# miniPCIE_Connector.net
KiCad netlist of a schematic drawn in Altium Designer
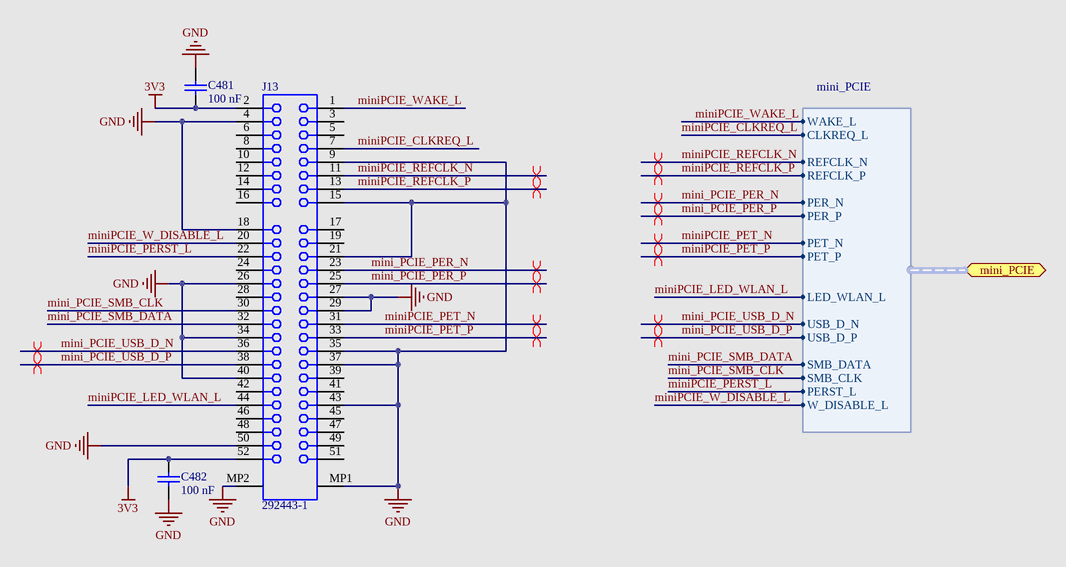
[diagram p0: miniPCIE_Connector.SchDoc]

(export (version "E")
  (design (tool "Eeschema 10.0.6"))
  (components
    (comp (ref "C481")
      (value "C1005X7R1E104M")
      (footprint "CAPC1005X55X10LL05")
      (description "Chip Capacitor, 0.1 uF, +/- 20%, 25 V, -55 to 125 degC, 0402 (1005 Metric), RoHS, Tape and Reel")
      (fields (field (name "TOLERANCE") "20%") (field (name "CAPACITANCE") "100 nF"))
      (libsource (lib "Altium Content Vault") (part "CAP-NP-2"))
    )
    (comp (ref "C482")
      (value "C1005X7R1E104M")
      (footprint "CAPC1005X55X10LL05")
      (description "Chip Capacitor, 0.1 uF, +/- 20%, 25 V, -55 to 125 degC, 0402 (1005 Metric), RoHS, Tape and Reel")
      (fields (field (name "TOLERANCE") "20%") (field (name "CAPACITANCE") "100 nF"))
      (libsource (lib "Altium Content Vault") (part "CAP-NP-2"))
    )
    (comp (ref "J13")
      (value "292443-1")
      (footprint "BTB-SM0-8-2H52F")
      (description "Board-to-Board Connector, SMT, Right Angle, Pitch 0.8mm, 52-Position, Female")
      (fields (field (name "PUBLISHER") "Altium"))
      (libsource (lib "Altium Content Vault") (part "CN-2S-2F-R52"))
    )
  )
  (nets
    (net (code "2") (name "/miniPCIE_CLKREQ_L") (class "Default")
      (node (ref "J13") (pin "7") (pinfunction "7_7") (pintype "passive"))
    )
    (net (code "3") (name "/miniPCIE_LED_WLAN_L") (class "Default")
      (node (ref "J13") (pin "44") (pinfunction "44_44") (pintype "passive"))
    )
    (net (code "4") (name "/miniPCIE_PERST_L") (class "Default")
      (node (ref "J13") (pin "22") (pinfunction "22_22") (pintype "passive"))
    )
    (net (code "5") (name "/miniPCIE_PET_N") (class "Default")
      (node (ref "J13") (pin "31") (pinfunction "31_31") (pintype "passive"))
    )
    (net (code "6") (name "/miniPCIE_PET_P") (class "Default")
      (node (ref "J13") (pin "33") (pinfunction "33_33") (pintype "passive"))
    )
    (net (code "7") (name "/miniPCIE_REFCLK_N") (class "Default")
      (node (ref "J13") (pin "11") (pinfunction "11_11") (pintype "passive"))
    )
    (net (code "8") (name "/miniPCIE_REFCLK_P") (class "Default")
      (node (ref "J13") (pin "13") (pinfunction "13_13") (pintype "passive"))
    )
    (net (code "9") (name "/miniPCIE_WAKE_L") (class "Default")
      (node (ref "J13") (pin "1") (pinfunction "1_1") (pintype "passive"))
    )
    (net (code "10") (name "/miniPCIE_W_DISABLE_L") (class "Default")
      (node (ref "J13") (pin "20") (pinfunction "20_20") (pintype "passive"))
    )
    (net (code "11") (name "/mini_PCIE_PER_N") (class "Default")
      (node (ref "J13") (pin "23") (pinfunction "23_23") (pintype "passive"))
    )
    (net (code "12") (name "/mini_PCIE_PER_P") (class "Default")
      (node (ref "J13") (pin "25") (pinfunction "25_25") (pintype "passive"))
    )
    (net (code "13") (name "/mini_PCIE_SMB_CLK") (class "Default")
      (node (ref "J13") (pin "30") (pinfunction "30_30") (pintype "passive"))
    )
    (net (code "14") (name "/mini_PCIE_SMB_DATA") (class "Default")
      (node (ref "J13") (pin "32") (pinfunction "32_32") (pintype "passive"))
    )
    (net (code "15") (name "/mini_PCIE_USB_D_N") (class "Default")
      (node (ref "J13") (pin "36") (pinfunction "36_36") (pintype "passive"))
    )
    (net (code "16") (name "/mini_PCIE_USB_D_P") (class "Default")
      (node (ref "J13") (pin "38") (pinfunction "38_38") (pintype "passive"))
    )
    (net (code "18") (name "3V3") (class "Default")
      (node (ref "C481") (pin "2") (pinfunction "2_2") (pintype "passive"))
      (node (ref "C482") (pin "1") (pinfunction "1_1") (pintype "passive"))
      (node (ref "J13") (pin "2") (pinfunction "2_2") (pintype "passive"))
      (node (ref "J13") (pin "52") (pinfunction "52_52") (pintype "passive"))
    )
    (net (code "19") (name "GND") (class "Default")
      (node (ref "C481") (pin "1") (pinfunction "1_1") (pintype "passive"))
      (node (ref "C482") (pin "2") (pinfunction "2_2") (pintype "passive"))
      (node (ref "J13") (pin "15") (pinfunction "15_15") (pintype "passive"))
      (node (ref "J13") (pin "18") (pinfunction "18_18") (pintype "passive"))
      (node (ref "J13") (pin "21") (pinfunction "21_21") (pintype "passive"))
      (node (ref "J13") (pin "26") (pinfunction "26_26") (pintype "passive"))
      (node (ref "J13") (pin "27") (pinfunction "27_27") (pintype "passive"))
      (node (ref "J13") (pin "29") (pinfunction "29_29") (pintype "passive"))
      (node (ref "J13") (pin "34") (pinfunction "34_34") (pintype "passive"))
      (node (ref "J13") (pin "35") (pinfunction "35_35") (pintype "passive"))
      (node (ref "J13") (pin "37") (pinfunction "37_37") (pintype "passive"))
      (node (ref "J13") (pin "4") (pinfunction "4_4") (pintype "passive"))
      (node (ref "J13") (pin "40") (pinfunction "40_40") (pintype "passive"))
      (node (ref "J13") (pin "43") (pinfunction "43_43") (pintype "passive"))
      (node (ref "J13") (pin "50") (pinfunction "50_50") (pintype "passive"))
      (node (ref "J13") (pin "9") (pinfunction "9_9") (pintype "passive"))
      (node (ref "J13") (pin "MP1") (pinfunction "53_MP1") (pintype "passive"))
      (node (ref "J13") (pin "MP2") (pinfunction "54_MP2") (pintype "passive"))
    )
    (net (code "20") (name "unconnected-(J13-Pad3)") (class "Default")
      (node (ref "J13") (pin "3") (pinfunction "3_3") (pintype "passive"))
    )
    (net (code "21") (name "unconnected-(J13-Pad5)") (class "Default")
      (node (ref "J13") (pin "5") (pinfunction "5_5") (pintype "passive"))
    )
    (net (code "22") (name "unconnected-(J13-Pad6)") (class "Default")
      (node (ref "J13") (pin "6") (pinfunction "6_6") (pintype "passive"))
    )
    (net (code "23") (name "unconnected-(J13-Pad8)") (class "Default")
      (node (ref "J13") (pin "8") (pinfunction "8_8") (pintype "passive"))
    )
    (net (code "24") (name "unconnected-(J13-Pad10)") (class "Default")
      (node (ref "J13") (pin "10") (pinfunction "10_10") (pintype "passive"))
    )
    (net (code "25") (name "unconnected-(J13-Pad12)") (class "Default")
      (node (ref "J13") (pin "12") (pinfunction "12_12") (pintype "passive"))
    )
    (net (code "26") (name "unconnected-(J13-Pad14)") (class "Default")
      (node (ref "J13") (pin "14") (pinfunction "14_14") (pintype "passive"))
    )
    (net (code "27") (name "unconnected-(J13-Pad16)") (class "Default")
      (node (ref "J13") (pin "16") (pinfunction "16_16") (pintype "passive"))
    )
    (net (code "28") (name "unconnected-(J13-Pad17)") (class "Default")
      (node (ref "J13") (pin "17") (pinfunction "17_17") (pintype "passive"))
    )
    (net (code "29") (name "unconnected-(J13-Pad19)") (class "Default")
      (node (ref "J13") (pin "19") (pinfunction "19_19") (pintype "passive"))
    )
    (net (code "30") (name "unconnected-(J13-Pad24)") (class "Default")
      (node (ref "J13") (pin "24") (pinfunction "24_24") (pintype "passive"))
    )
    (net (code "31") (name "unconnected-(J13-Pad28)") (class "Default")
      (node (ref "J13") (pin "28") (pinfunction "28_28") (pintype "passive"))
    )
    (net (code "32") (name "unconnected-(J13-Pad39)") (class "Default")
      (node (ref "J13") (pin "39") (pinfunction "39_39") (pintype "passive"))
    )
    (net (code "33") (name "unconnected-(J13-Pad41)") (class "Default")
      (node (ref "J13") (pin "41") (pinfunction "41_41") (pintype "passive"))
    )
    (net (code "34") (name "unconnected-(J13-Pad42)") (class "Default")
      (node (ref "J13") (pin "42") (pinfunction "42_42") (pintype "passive"))
    )
    (net (code "35") (name "unconnected-(J13-Pad45)") (class "Default")
      (node (ref "J13") (pin "45") (pinfunction "45_45") (pintype "passive"))
    )
    (net (code "36") (name "unconnected-(J13-Pad46)") (class "Default")
      (node (ref "J13") (pin "46") (pinfunction "46_46") (pintype "passive"))
    )
    (net (code "37") (name "unconnected-(J13-Pad47)") (class "Default")
      (node (ref "J13") (pin "47") (pinfunction "47_47") (pintype "passive"))
    )
    (net (code "38") (name "unconnected-(J13-Pad48)") (class "Default")
      (node (ref "J13") (pin "48") (pinfunction "48_48") (pintype "passive"))
    )
    (net (code "39") (name "unconnected-(J13-Pad49)") (class "Default")
      (node (ref "J13") (pin "49") (pinfunction "49_49") (pintype "passive"))
    )
    (net (code "40") (name "unconnected-(J13-Pad51)") (class "Default")
      (node (ref "J13") (pin "51") (pinfunction "51_51") (pintype "passive"))
    )
  )
)
